# receiver_2.net
KiCad netlist of a schematic drawn in Altium Designer
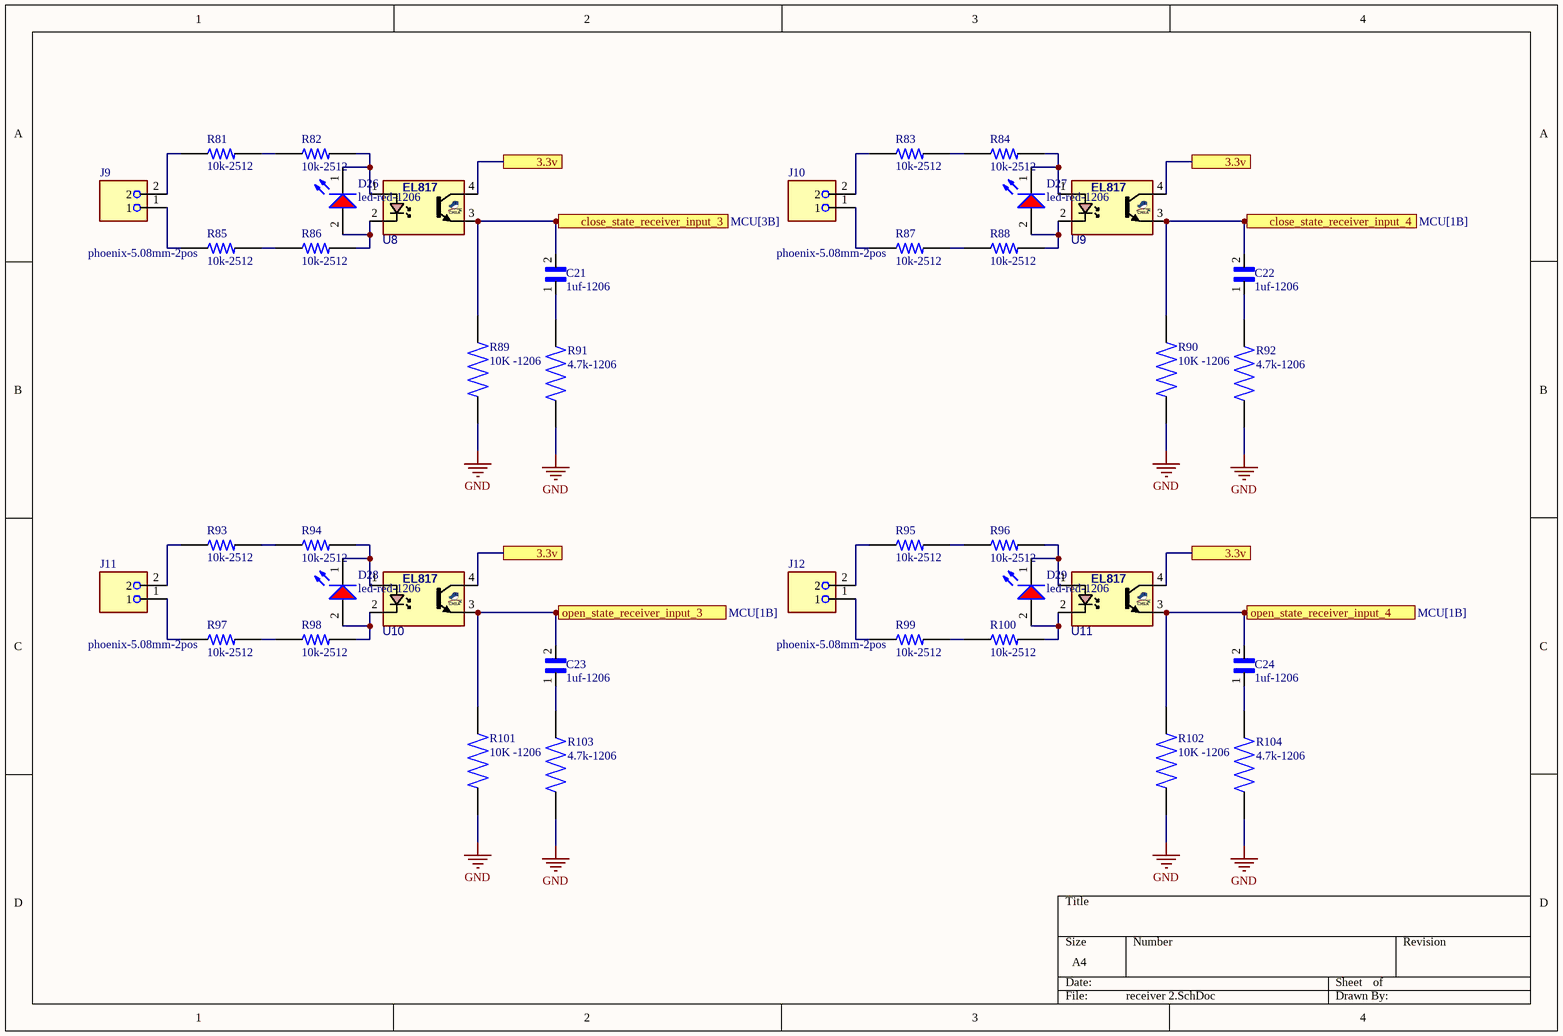
[diagram p0: receiver 2.SchDoc]

(export (version "E")
  (design (tool "Eeschema 10.0.6"))
  (components
    (comp (ref "C21")
      (value "1uf-1206")
      (footprint "CAPC3216X180N")
      (description "1ÂµF Â±20% 50V Ceramic Capacitor X8R 1206 (3216 Metric)")
      (fields (field (name "MF") "TDK") (field (name "MP") "CGA5L3X8R1H105M160AB"))
      (libsource (lib "cap-1206") (part "CGA5L3X8R1H105M160AB"))
    )
    (comp (ref "C22")
      (value "1uf-1206")
      (footprint "CAPC3216X180N")
      (description "1ÂµF Â±20% 50V Ceramic Capacitor X8R 1206 (3216 Metric)")
      (fields (field (name "MF") "TDK") (field (name "MP") "CGA5L3X8R1H105M160AB"))
      (libsource (lib "cap-1206") (part "CGA5L3X8R1H105M160AB"))
    )
    (comp (ref "C23")
      (value "1uf-1206")
      (footprint "CAPC3216X180N")
      (description "1ÂµF Â±20% 50V Ceramic Capacitor X8R 1206 (3216 Metric)")
      (fields (field (name "MF") "TDK") (field (name "MP") "CGA5L3X8R1H105M160AB"))
      (libsource (lib "cap-1206") (part "CGA5L3X8R1H105M160AB"))
    )
    (comp (ref "C24")
      (value "1uf-1206")
      (footprint "CAPC3216X180N")
      (description "1ÂµF Â±20% 50V Ceramic Capacitor X8R 1206 (3216 Metric)")
      (fields (field (name "MF") "TDK") (field (name "MP") "CGA5L3X8R1H105M160AB"))
      (libsource (lib "cap-1206") (part "CGA5L3X8R1H105M160AB"))
    )
    (comp (ref "D26")
      (value "led-red-1206")
      (footprint "WL-SMRW_1206 dome_normal use")
      (description "WL-SMRW Mono-color Reverse mount Waterclear, SMT, size 1206 dome, Red, 2V, 20°")
      (fields
        (field (name "MANUFACTURER PART NUMBER") "156120RS82500")
        (field (name "MANUFACTURER") "Wurth Elektronik")
      )
      (libsource (lib "led-1206") (part "156120RS82500"))
    )
    (comp (ref "D27")
      (value "led-red-1206")
      (footprint "WL-SMRW_1206 dome_normal use")
      (description "WL-SMRW Mono-color Reverse mount Waterclear, SMT, size 1206 dome, Red, 2V, 20°")
      (fields
        (field (name "MANUFACTURER PART NUMBER") "156120RS82500")
        (field (name "MANUFACTURER") "Wurth Elektronik")
      )
      (libsource (lib "led-1206") (part "156120RS82500"))
    )
    (comp (ref "D28")
      (value "led-red-1206")
      (footprint "WL-SMRW_1206 dome_normal use")
      (description "WL-SMRW Mono-color Reverse mount Waterclear, SMT, size 1206 dome, Red, 2V, 20°")
      (fields
        (field (name "MANUFACTURER PART NUMBER") "156120RS82500")
        (field (name "MANUFACTURER") "Wurth Elektronik")
      )
      (libsource (lib "led-1206") (part "156120RS82500"))
    )
    (comp (ref "D29")
      (value "led-red-1206")
      (footprint "WL-SMRW_1206 dome_normal use")
      (description "WL-SMRW Mono-color Reverse mount Waterclear, SMT, size 1206 dome, Red, 2V, 20°")
      (fields
        (field (name "MANUFACTURER PART NUMBER") "156120RS82500")
        (field (name "MANUFACTURER") "Wurth Elektronik")
      )
      (libsource (lib "led-1206") (part "156120RS82500"))
    )
    (comp (ref "J9")
      (value "phoenix-5.08mm-2pos")
      (footprint "PHOENIX_1715721")
      (fields (field (name "MP") "1715721"))
      (libsource (lib "phoenix-2pos") (part "1715721"))
    )
    (comp (ref "J10")
      (value "phoenix-5.08mm-2pos")
      (footprint "PHOENIX_1715721")
      (fields (field (name "MP") "1715721"))
      (libsource (lib "phoenix-2pos") (part "1715721"))
    )
    (comp (ref "J11")
      (value "phoenix-5.08mm-2pos")
      (footprint "PHOENIX_1715721")
      (fields (field (name "MP") "1715721"))
      (libsource (lib "phoenix-2pos") (part "1715721"))
    )
    (comp (ref "J12")
      (value "phoenix-5.08mm-2pos")
      (footprint "PHOENIX_1715721")
      (fields (field (name "MP") "1715721"))
      (libsource (lib "phoenix-2pos") (part "1715721"))
    )
    (comp (ref "R81")
      (value "10k-2512")
      (footprint "RESC6331X70N")
      (description "18 kOhms Â±5% 1.5W Chip Resistor 2512 (6432 Metric) Pulse Withstanding Thick Film")
      (fields (field (name "MF") "TE Connectivity") (field (name "MP") "5-2176246-2"))
      (libsource (lib "resistor-2512") (part "5-2176246-2"))
    )
    (comp (ref "R82")
      (value "10k-2512")
      (footprint "RESC6331X70N")
      (description "18 kOhms Â±5% 1.5W Chip Resistor 2512 (6432 Metric) Pulse Withstanding Thick Film")
      (fields (field (name "MF") "TE Connectivity") (field (name "MP") "5-2176246-2"))
      (libsource (lib "resistor-2512") (part "5-2176246-2"))
    )
    (comp (ref "R83")
      (value "10k-2512")
      (footprint "RESC6331X70N")
      (description "18 kOhms Â±5% 1.5W Chip Resistor 2512 (6432 Metric) Pulse Withstanding Thick Film")
      (fields (field (name "MF") "TE Connectivity") (field (name "MP") "5-2176246-2"))
      (libsource (lib "resistor-2512") (part "5-2176246-2"))
    )
    (comp (ref "R84")
      (value "10k-2512")
      (footprint "RESC6331X70N")
      (description "18 kOhms Â±5% 1.5W Chip Resistor 2512 (6432 Metric) Pulse Withstanding Thick Film")
      (fields (field (name "MF") "TE Connectivity") (field (name "MP") "5-2176246-2"))
      (libsource (lib "resistor-2512") (part "5-2176246-2"))
    )
    (comp (ref "R85")
      (value "10k-2512")
      (footprint "RESC6331X70N")
      (description "18 kOhms Â±5% 1.5W Chip Resistor 2512 (6432 Metric) Pulse Withstanding Thick Film")
      (fields (field (name "MF") "TE Connectivity") (field (name "MP") "5-2176246-2"))
      (libsource (lib "resistor-2512") (part "5-2176246-2"))
    )
    (comp (ref "R86")
      (value "10k-2512")
      (footprint "RESC6331X70N")
      (description "18 kOhms Â±5% 1.5W Chip Resistor 2512 (6432 Metric) Pulse Withstanding Thick Film")
      (fields (field (name "MF") "TE Connectivity") (field (name "MP") "5-2176246-2"))
      (libsource (lib "resistor-2512") (part "5-2176246-2"))
    )
    (comp (ref "R87")
      (value "10k-2512")
      (footprint "RESC6331X70N")
      (description "18 kOhms Â±5% 1.5W Chip Resistor 2512 (6432 Metric) Pulse Withstanding Thick Film")
      (fields (field (name "MF") "TE Connectivity") (field (name "MP") "5-2176246-2"))
      (libsource (lib "resistor-2512") (part "5-2176246-2"))
    )
    (comp (ref "R88")
      (value "10k-2512")
      (footprint "RESC6331X70N")
      (description "18 kOhms Â±5% 1.5W Chip Resistor 2512 (6432 Metric) Pulse Withstanding Thick Film")
      (fields (field (name "MF") "TE Connectivity") (field (name "MP") "5-2176246-2"))
      (libsource (lib "resistor-2512") (part "5-2176246-2"))
    )
    (comp (ref "R89")
      (value "10K -1206")
      (footprint "RESC3015X65N")
      (description "Res Thin Film 1206 10K Ohm 0.1% 1/8W Â±25ppm/Â°C Molded SMD SMD Paper T/R")
      (fields (field (name "MF") "TE Connectivity") (field (name "MP") "CPF1206B10KE1"))
      (libsource (lib "resistor-1206") (part "CPF1206B10KE1"))
    )
    (comp (ref "R90")
      (value "10K -1206")
      (footprint "RESC3015X65N")
      (description "Res Thin Film 1206 10K Ohm 0.1% 1/8W Â±25ppm/Â°C Molded SMD SMD Paper T/R")
      (fields (field (name "MF") "TE Connectivity") (field (name "MP") "CPF1206B10KE1"))
      (libsource (lib "resistor-1206") (part "CPF1206B10KE1"))
    )
    (comp (ref "R91")
      (value "4.7k-1206")
      (footprint "RESC3015X65N")
      (description "Res Thin Film 1206 10K Ohm 0.1% 1/8W Â±25ppm/Â°C Molded SMD SMD Paper T/R")
      (fields (field (name "MF") "TE Connectivity") (field (name "MP") "CPF1206B10KE1"))
      (libsource (lib "resistor-1206") (part "CPF1206B10KE1"))
    )
    (comp (ref "R92")
      (value "4.7k-1206")
      (footprint "RESC3015X65N")
      (description "Res Thin Film 1206 10K Ohm 0.1% 1/8W Â±25ppm/Â°C Molded SMD SMD Paper T/R")
      (fields (field (name "MF") "TE Connectivity") (field (name "MP") "CPF1206B10KE1"))
      (libsource (lib "resistor-1206") (part "CPF1206B10KE1"))
    )
    (comp (ref "R93")
      (value "10k-2512")
      (footprint "RESC6331X70N")
      (description "18 kOhms Â±5% 1.5W Chip Resistor 2512 (6432 Metric) Pulse Withstanding Thick Film")
      (fields (field (name "MF") "TE Connectivity") (field (name "MP") "5-2176246-2"))
      (libsource (lib "resistor-2512") (part "5-2176246-2"))
    )
    (comp (ref "R94")
      (value "10k-2512")
      (footprint "RESC6331X70N")
      (description "18 kOhms Â±5% 1.5W Chip Resistor 2512 (6432 Metric) Pulse Withstanding Thick Film")
      (fields (field (name "MF") "TE Connectivity") (field (name "MP") "5-2176246-2"))
      (libsource (lib "resistor-2512") (part "5-2176246-2"))
    )
    (comp (ref "R95")
      (value "10k-2512")
      (footprint "RESC6331X70N")
      (description "18 kOhms Â±5% 1.5W Chip Resistor 2512 (6432 Metric) Pulse Withstanding Thick Film")
      (fields (field (name "MF") "TE Connectivity") (field (name "MP") "5-2176246-2"))
      (libsource (lib "resistor-2512") (part "5-2176246-2"))
    )
    (comp (ref "R96")
      (value "10k-2512")
      (footprint "RESC6331X70N")
      (description "18 kOhms Â±5% 1.5W Chip Resistor 2512 (6432 Metric) Pulse Withstanding Thick Film")
      (fields (field (name "MF") "TE Connectivity") (field (name "MP") "5-2176246-2"))
      (libsource (lib "resistor-2512") (part "5-2176246-2"))
    )
    (comp (ref "R97")
      (value "10k-2512")
      (footprint "RESC6331X70N")
      (description "18 kOhms Â±5% 1.5W Chip Resistor 2512 (6432 Metric) Pulse Withstanding Thick Film")
      (fields (field (name "MF") "TE Connectivity") (field (name "MP") "5-2176246-2"))
      (libsource (lib "resistor-2512") (part "5-2176246-2"))
    )
    (comp (ref "R98")
      (value "10k-2512")
      (footprint "RESC6331X70N")
      (description "18 kOhms Â±5% 1.5W Chip Resistor 2512 (6432 Metric) Pulse Withstanding Thick Film")
      (fields (field (name "MF") "TE Connectivity") (field (name "MP") "5-2176246-2"))
      (libsource (lib "resistor-2512") (part "5-2176246-2"))
    )
    (comp (ref "R99")
      (value "10k-2512")
      (footprint "RESC6331X70N")
      (description "18 kOhms Â±5% 1.5W Chip Resistor 2512 (6432 Metric) Pulse Withstanding Thick Film")
      (fields (field (name "MF") "TE Connectivity") (field (name "MP") "5-2176246-2"))
      (libsource (lib "resistor-2512") (part "5-2176246-2"))
    )
    (comp (ref "R100")
      (value "10k-2512")
      (footprint "RESC6331X70N")
      (description "18 kOhms Â±5% 1.5W Chip Resistor 2512 (6432 Metric) Pulse Withstanding Thick Film")
      (fields (field (name "MF") "TE Connectivity") (field (name "MP") "5-2176246-2"))
      (libsource (lib "resistor-2512") (part "5-2176246-2"))
    )
    (comp (ref "R101")
      (value "10K -1206")
      (footprint "RESC3015X65N")
      (description "Res Thin Film 1206 10K Ohm 0.1% 1/8W Â±25ppm/Â°C Molded SMD SMD Paper T/R")
      (fields (field (name "MF") "TE Connectivity") (field (name "MP") "CPF1206B10KE1"))
      (libsource (lib "resistor-1206") (part "CPF1206B10KE1"))
    )
    (comp (ref "R102")
      (value "10K -1206")
      (footprint "RESC3015X65N")
      (description "Res Thin Film 1206 10K Ohm 0.1% 1/8W Â±25ppm/Â°C Molded SMD SMD Paper T/R")
      (fields (field (name "MF") "TE Connectivity") (field (name "MP") "CPF1206B10KE1"))
      (libsource (lib "resistor-1206") (part "CPF1206B10KE1"))
    )
    (comp (ref "R103")
      (value "4.7k-1206")
      (footprint "RESC3015X65N")
      (description "Res Thin Film 1206 10K Ohm 0.1% 1/8W Â±25ppm/Â°C Molded SMD SMD Paper T/R")
      (fields (field (name "MF") "TE Connectivity") (field (name "MP") "CPF1206B10KE1"))
      (libsource (lib "resistor-1206") (part "CPF1206B10KE1"))
    )
    (comp (ref "R104")
      (value "4.7k-1206")
      (footprint "RESC3015X65N")
      (description "Res Thin Film 1206 10K Ohm 0.1% 1/8W Â±25ppm/Â°C Molded SMD SMD Paper T/R")
      (fields (field (name "MF") "TE Connectivity") (field (name "MP") "CPF1206B10KE1"))
      (libsource (lib "resistor-1206") (part "CPF1206B10KE1"))
    )
    (comp (ref "U8")
      (value "EL817")
      (footprint "DIP_4SMD")
      (description "OPTOCOUPLER, TRANSISTOR, 4PIN")
      (libsource (lib "optocoupler") (part "OPTC_TR4P_EL817_SMD"))
    )
    (comp (ref "U9")
      (value "EL817")
      (footprint "DIP_4SMD")
      (description "OPTOCOUPLER, TRANSISTOR, 4PIN")
      (libsource (lib "optocoupler") (part "OPTC_TR4P_EL817_SMD"))
    )
    (comp (ref "U10")
      (value "EL817")
      (footprint "DIP_4SMD")
      (description "OPTOCOUPLER, TRANSISTOR, 4PIN")
      (libsource (lib "optocoupler") (part "OPTC_TR4P_EL817_SMD"))
    )
    (comp (ref "U11")
      (value "EL817")
      (footprint "DIP_4SMD")
      (description "OPTOCOUPLER, TRANSISTOR, 4PIN")
      (libsource (lib "optocoupler") (part "OPTC_TR4P_EL817_SMD"))
    )
  )
  (nets
    (net (code "1") (name "/3.3v") (class "Default")
      (node (ref "U10") (pin "4") (pinfunction "C_4") (pintype "passive"))
      (node (ref "U11") (pin "4") (pinfunction "C_4") (pintype "passive"))
      (node (ref "U8") (pin "4") (pinfunction "C_4") (pintype "passive"))
      (node (ref "U9") (pin "4") (pinfunction "C_4") (pintype "passive"))
    )
    (net (code "2") (name "/close_state_receiver_input_3") (class "Default")
      (node (ref "C21") (pin "2") (pinfunction "2_2") (pintype "passive"))
      (node (ref "R89") (pin "2") (pinfunction "2_2") (pintype "passive"))
      (node (ref "U8") (pin "3") (pinfunction "E_3") (pintype "passive"))
    )
    (net (code "3") (name "/close_state_receiver_input_4") (class "Default")
      (node (ref "C22") (pin "2") (pinfunction "2_2") (pintype "passive"))
      (node (ref "R90") (pin "2") (pinfunction "2_2") (pintype "passive"))
      (node (ref "U9") (pin "3") (pinfunction "E_3") (pintype "passive"))
    )
    (net (code "4") (name "/open_state_receiver_input_3") (class "Default")
      (node (ref "C23") (pin "2") (pinfunction "2_2") (pintype "passive"))
      (node (ref "R101") (pin "2") (pinfunction "2_2") (pintype "passive"))
      (node (ref "U10") (pin "3") (pinfunction "E_3") (pintype "passive"))
    )
    (net (code "5") (name "/open_state_receiver_input_4") (class "Default")
      (node (ref "C24") (pin "2") (pinfunction "2_2") (pintype "passive"))
      (node (ref "R102") (pin "2") (pinfunction "2_2") (pintype "passive"))
      (node (ref "U11") (pin "3") (pinfunction "E_3") (pintype "passive"))
    )
    (net (code "6") (name "GND") (class "Default")
      (node (ref "R101") (pin "1") (pinfunction "1_1") (pintype "passive"))
      (node (ref "R102") (pin "1") (pinfunction "1_1") (pintype "passive"))
      (node (ref "R103") (pin "1") (pinfunction "1_1") (pintype "passive"))
      (node (ref "R104") (pin "1") (pinfunction "1_1") (pintype "passive"))
      (node (ref "R89") (pin "1") (pinfunction "1_1") (pintype "passive"))
      (node (ref "R90") (pin "1") (pinfunction "1_1") (pintype "passive"))
      (node (ref "R91") (pin "1") (pinfunction "1_1") (pintype "passive"))
      (node (ref "R92") (pin "1") (pinfunction "1_1") (pintype "passive"))
    )
    (net (code "7") (name "Net-(C21-Pad1)") (class "Default")
      (node (ref "C21") (pin "1") (pinfunction "1_1") (pintype "passive"))
      (node (ref "R91") (pin "2") (pinfunction "2_2") (pintype "passive"))
    )
    (net (code "8") (name "Net-(C22-Pad1)") (class "Default")
      (node (ref "C22") (pin "1") (pinfunction "1_1") (pintype "passive"))
      (node (ref "R92") (pin "2") (pinfunction "2_2") (pintype "passive"))
    )
    (net (code "9") (name "Net-(C23-Pad1)") (class "Default")
      (node (ref "C23") (pin "1") (pinfunction "1_1") (pintype "passive"))
      (node (ref "R103") (pin "2") (pinfunction "2_2") (pintype "passive"))
    )
    (net (code "10") (name "Net-(C24-Pad1)") (class "Default")
      (node (ref "C24") (pin "1") (pinfunction "1_1") (pintype "passive"))
      (node (ref "R104") (pin "2") (pinfunction "2_2") (pintype "passive"))
    )
    (net (code "11") (name "Net-(D26-A)") (class "Default")
      (node (ref "D26") (pin "2") (pinfunction "A_2") (pintype "passive"))
      (node (ref "R86") (pin "2") (pinfunction "2_2") (pintype "passive"))
      (node (ref "U8") (pin "2") (pinfunction "K_2") (pintype "passive"))
    )
    (net (code "12") (name "Net-(D26-K)") (class "Default")
      (node (ref "D26") (pin "1") (pinfunction "K_1") (pintype "passive"))
      (node (ref "R82") (pin "2") (pinfunction "2_2") (pintype "passive"))
      (node (ref "U8") (pin "1") (pinfunction "A_1") (pintype "passive"))
    )
    (net (code "13") (name "Net-(D27-A)") (class "Default")
      (node (ref "D27") (pin "2") (pinfunction "A_2") (pintype "passive"))
      (node (ref "R88") (pin "2") (pinfunction "2_2") (pintype "passive"))
      (node (ref "U9") (pin "2") (pinfunction "K_2") (pintype "passive"))
    )
    (net (code "14") (name "Net-(D27-K)") (class "Default")
      (node (ref "D27") (pin "1") (pinfunction "K_1") (pintype "passive"))
      (node (ref "R84") (pin "2") (pinfunction "2_2") (pintype "passive"))
      (node (ref "U9") (pin "1") (pinfunction "A_1") (pintype "passive"))
    )
    (net (code "15") (name "Net-(D28-A)") (class "Default")
      (node (ref "D28") (pin "2") (pinfunction "A_2") (pintype "passive"))
      (node (ref "R98") (pin "2") (pinfunction "2_2") (pintype "passive"))
      (node (ref "U10") (pin "2") (pinfunction "K_2") (pintype "passive"))
    )
    (net (code "16") (name "Net-(D28-K)") (class "Default")
      (node (ref "D28") (pin "1") (pinfunction "K_1") (pintype "passive"))
      (node (ref "R94") (pin "2") (pinfunction "2_2") (pintype "passive"))
      (node (ref "U10") (pin "1") (pinfunction "A_1") (pintype "passive"))
    )
    (net (code "17") (name "Net-(D29-A)") (class "Default")
      (node (ref "D29") (pin "2") (pinfunction "A_2") (pintype "passive"))
      (node (ref "R100") (pin "2") (pinfunction "2_2") (pintype "passive"))
      (node (ref "U11") (pin "2") (pinfunction "K_2") (pintype "passive"))
    )
    (net (code "18") (name "Net-(D29-K)") (class "Default")
      (node (ref "D29") (pin "1") (pinfunction "K_1") (pintype "passive"))
      (node (ref "R96") (pin "2") (pinfunction "2_2") (pintype "passive"))
      (node (ref "U11") (pin "1") (pinfunction "A_1") (pintype "passive"))
    )
    (net (code "19") (name "Net-(J9-Pad1)") (class "Default")
      (node (ref "J9") (pin "1") (pinfunction "1_1") (pintype "passive"))
      (node (ref "R85") (pin "1") (pinfunction "1_1") (pintype "passive"))
    )
    (net (code "20") (name "Net-(J9-Pad2)") (class "Default")
      (node (ref "J9") (pin "2") (pinfunction "2_2") (pintype "passive"))
      (node (ref "R81") (pin "1") (pinfunction "1_1") (pintype "passive"))
    )
    (net (code "21") (name "Net-(J10-Pad1)") (class "Default")
      (node (ref "J10") (pin "1") (pinfunction "1_1") (pintype "passive"))
      (node (ref "R87") (pin "1") (pinfunction "1_1") (pintype "passive"))
    )
    (net (code "22") (name "Net-(J10-Pad2)") (class "Default")
      (node (ref "J10") (pin "2") (pinfunction "2_2") (pintype "passive"))
      (node (ref "R83") (pin "1") (pinfunction "1_1") (pintype "passive"))
    )
    (net (code "23") (name "Net-(J11-Pad1)") (class "Default")
      (node (ref "J11") (pin "1") (pinfunction "1_1") (pintype "passive"))
      (node (ref "R97") (pin "1") (pinfunction "1_1") (pintype "passive"))
    )
    (net (code "24") (name "Net-(J11-Pad2)") (class "Default")
      (node (ref "J11") (pin "2") (pinfunction "2_2") (pintype "passive"))
      (node (ref "R93") (pin "1") (pinfunction "1_1") (pintype "passive"))
    )
    (net (code "25") (name "Net-(J12-Pad1)") (class "Default")
      (node (ref "J12") (pin "1") (pinfunction "1_1") (pintype "passive"))
      (node (ref "R99") (pin "1") (pinfunction "1_1") (pintype "passive"))
    )
    (net (code "26") (name "Net-(J12-Pad2)") (class "Default")
      (node (ref "J12") (pin "2") (pinfunction "2_2") (pintype "passive"))
      (node (ref "R95") (pin "1") (pinfunction "1_1") (pintype "passive"))
    )
    (net (code "27") (name "Net-(R81-Pad2)") (class "Default")
      (node (ref "R81") (pin "2") (pinfunction "2_2") (pintype "passive"))
      (node (ref "R82") (pin "1") (pinfunction "1_1") (pintype "passive"))
    )
    (net (code "28") (name "Net-(R83-Pad2)") (class "Default")
      (node (ref "R83") (pin "2") (pinfunction "2_2") (pintype "passive"))
      (node (ref "R84") (pin "1") (pinfunction "1_1") (pintype "passive"))
    )
    (net (code "29") (name "Net-(R85-Pad2)") (class "Default")
      (node (ref "R85") (pin "2") (pinfunction "2_2") (pintype "passive"))
      (node (ref "R86") (pin "1") (pinfunction "1_1") (pintype "passive"))
    )
    (net (code "30") (name "Net-(R87-Pad2)") (class "Default")
      (node (ref "R87") (pin "2") (pinfunction "2_2") (pintype "passive"))
      (node (ref "R88") (pin "1") (pinfunction "1_1") (pintype "passive"))
    )
    (net (code "31") (name "Net-(R93-Pad2)") (class "Default")
      (node (ref "R93") (pin "2") (pinfunction "2_2") (pintype "passive"))
      (node (ref "R94") (pin "1") (pinfunction "1_1") (pintype "passive"))
    )
    (net (code "32") (name "Net-(R95-Pad2)") (class "Default")
      (node (ref "R95") (pin "2") (pinfunction "2_2") (pintype "passive"))
      (node (ref "R96") (pin "1") (pinfunction "1_1") (pintype "passive"))
    )
    (net (code "33") (name "Net-(R97-Pad2)") (class "Default")
      (node (ref "R97") (pin "2") (pinfunction "2_2") (pintype "passive"))
      (node (ref "R98") (pin "1") (pinfunction "1_1") (pintype "passive"))
    )
    (net (code "34") (name "Net-(R100-Pad1)") (class "Default")
      (node (ref "R100") (pin "1") (pinfunction "1_1") (pintype "passive"))
      (node (ref "R99") (pin "2") (pinfunction "2_2") (pintype "passive"))
    )
  )
)
